# SNES-3Chip_MR_QID.net
KiCad netlist of a schematic drawn in EAGLE
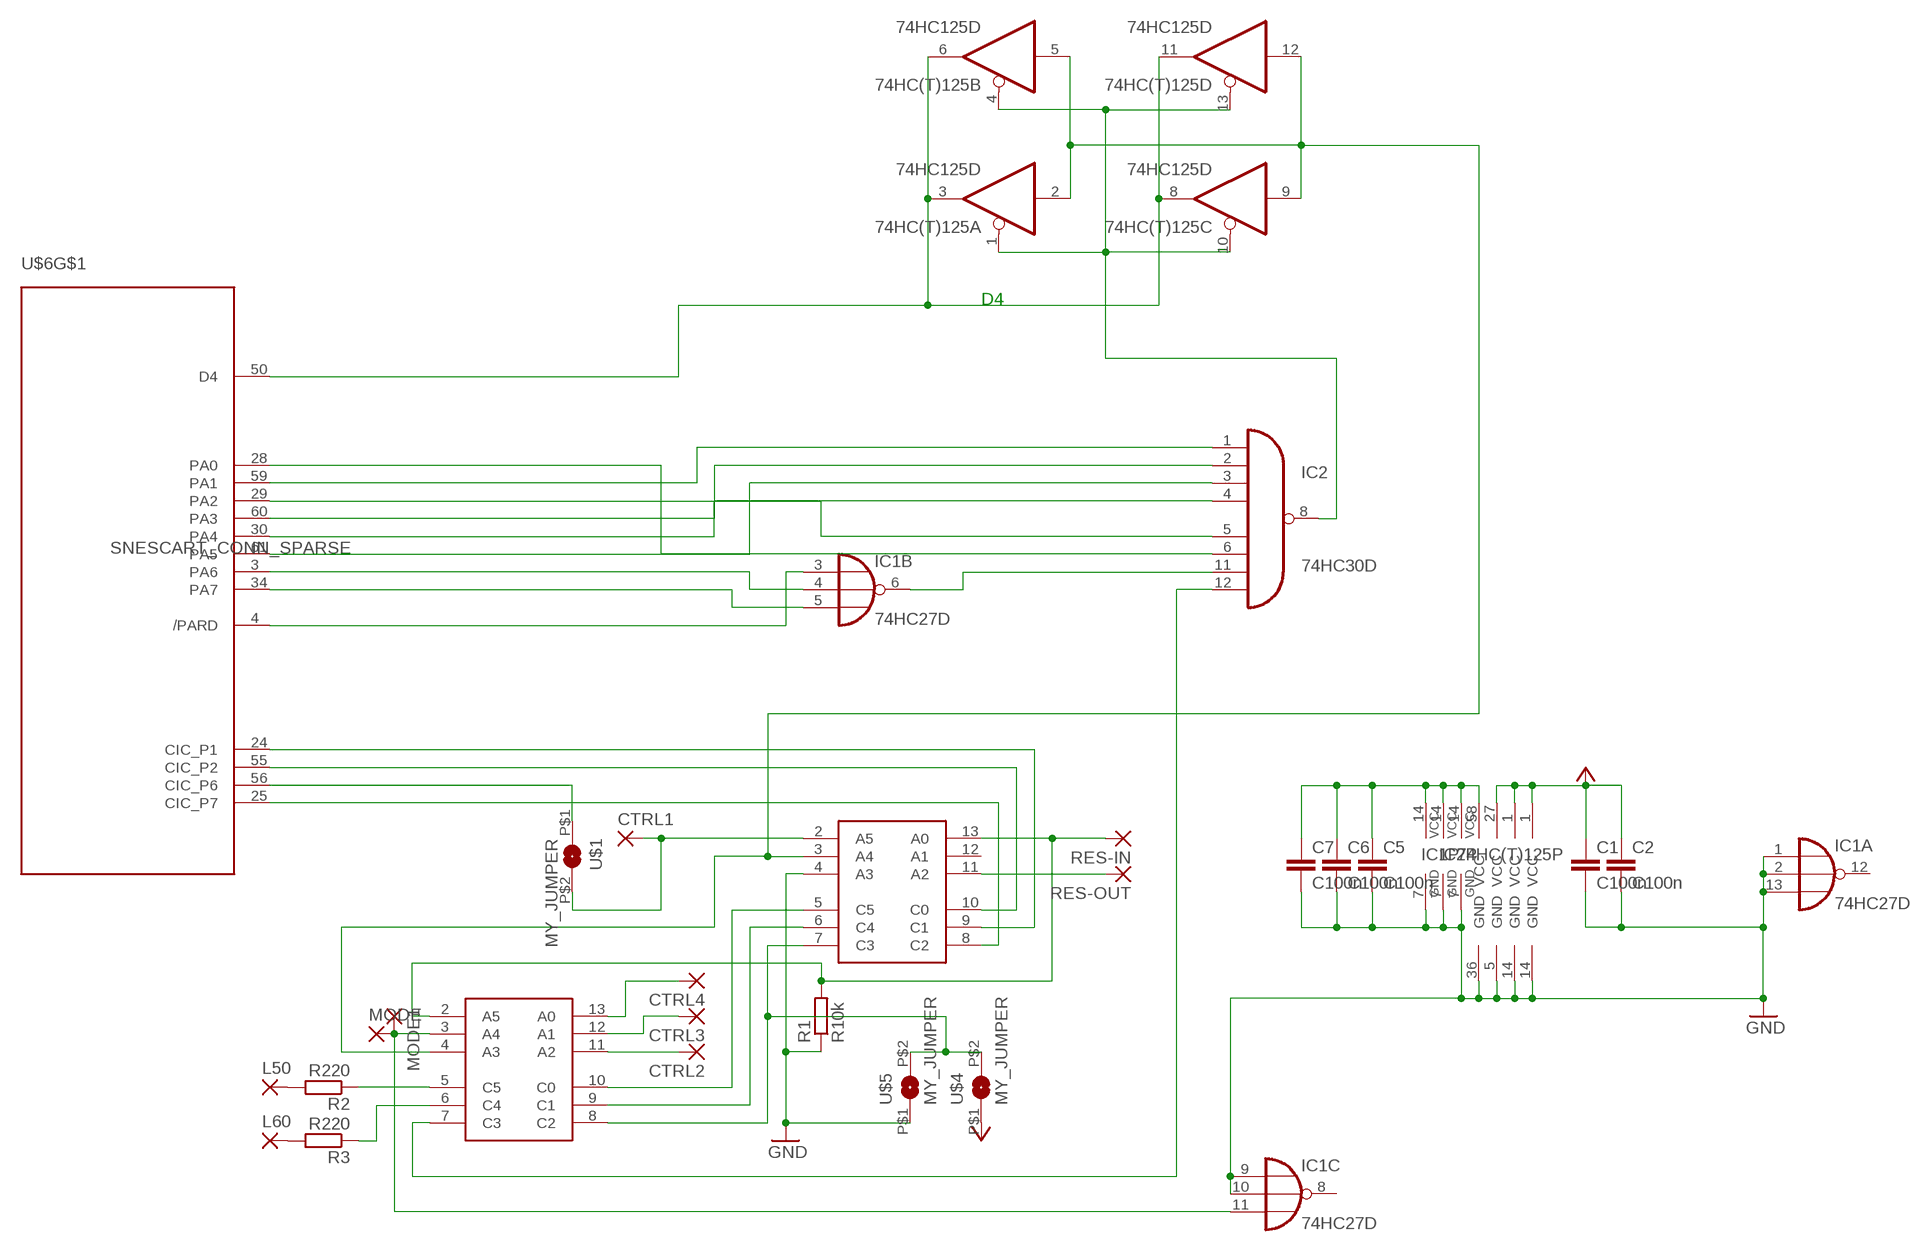
[diagram p0: schematic, sheet 1]

(export (version "E")
  (design (tool "Eeschema 10.0.6"))
  (components
    (comp (ref "74HC(T)125")
      (value "74HC125D")
      (footprint "eagle-import:SO14")
      (libsource (lib "eagle-import") (part "74125DHC"))
    )
    (comp (ref "C1")
      (value "C100n")
      (footprint "eagle-import:Z0805")
      (libsource (lib "eagle-import") (part "C0805"))
    )
    (comp (ref "C2")
      (value "C100n")
      (footprint "eagle-import:Z0805")
      (libsource (lib "eagle-import") (part "C0805"))
    )
    (comp (ref "C5")
      (value "C100n")
      (footprint "eagle-import:Z0805")
      (libsource (lib "eagle-import") (part "C0805"))
    )
    (comp (ref "C6")
      (value "C100n")
      (footprint "eagle-import:Z0805")
      (libsource (lib "eagle-import") (part "C0805"))
    )
    (comp (ref "C7")
      (value "C100n")
      (footprint "eagle-import:Z0805")
      (libsource (lib "eagle-import") (part "C0805"))
    )
    (comp (ref "CTRL1")
      (value "SMD2")
      (footprint "eagle-import:SMD1,27-2,54")
      (libsource (lib "eagle-import") (part "SMD2"))
    )
    (comp (ref "CTRL2")
      (value "SMD2")
      (footprint "eagle-import:SMD1,27-2,54")
      (libsource (lib "eagle-import") (part "SMD2"))
    )
    (comp (ref "CTRL3")
      (value "SMD2")
      (footprint "eagle-import:SMD1,27-2,54")
      (libsource (lib "eagle-import") (part "SMD2"))
    )
    (comp (ref "CTRL4")
      (value "SMD2")
      (footprint "eagle-import:SMD1,27-2,54")
      (libsource (lib "eagle-import") (part "SMD2"))
    )
    (comp (ref "IC1")
      (value "74HC27D")
      (footprint "eagle-import:SO14")
      (libsource (lib "eagle-import") (part "7427DHC"))
    )
    (comp (ref "IC2")
      (value "74HC30D")
      (footprint "eagle-import:SO14")
      (libsource (lib "eagle-import") (part "7430DHC"))
    )
    (comp (ref "L50")
      (value "SMD2")
      (footprint "eagle-import:SMD1,27-2,54")
      (libsource (lib "eagle-import") (part "SMD2"))
    )
    (comp (ref "L60")
      (value "SMD2")
      (footprint "eagle-import:SMD1,27-2,54")
      (libsource (lib "eagle-import") (part "SMD2"))
    )
    (comp (ref "MODE")
      (value "SMD2")
      (footprint "eagle-import:SMD1,27-2,54")
      (libsource (lib "eagle-import") (part "SMD2"))
    )
    (comp (ref "MODE1")
      (value "SMD2")
      (footprint "eagle-import:SMD1,27-2,54")
      (libsource (lib "eagle-import") (part "SMD2"))
    )
    (comp (ref "R1")
      (value "R10k")
      (footprint "eagle-import:Z0805")
      (libsource (lib "eagle-import") (part "R0805"))
    )
    (comp (ref "R2")
      (value "R220")
      (footprint "eagle-import:Z0805")
      (libsource (lib "eagle-import") (part "R0805"))
    )
    (comp (ref "R3")
      (value "R220")
      (footprint "eagle-import:Z0805")
      (libsource (lib "eagle-import") (part "R0805"))
    )
    (comp (ref "RES-IN")
      (value "SMD2")
      (footprint "eagle-import:SMD1,27-2,54")
      (libsource (lib "eagle-import") (part "SMD2"))
    )
    (comp (ref "RES-OUT")
      (value "SMD2")
      (footprint "eagle-import:SMD1,27-2,54")
      (libsource (lib "eagle-import") (part "SMD2"))
    )
    (comp (ref "U$1")
      (value "MY_JUMPER")
      (footprint "eagle-import:MYJUMP")
      (libsource (lib "eagle-import") (part "MY_JUMPER"))
    )
    (comp (ref "U$2")
      (value "PIC16F630_SIMPLE")
      (footprint "eagle-import:PIC16F630")
      (libsource (lib "eagle-import") (part "PIC16F630_SIMPLE"))
    )
    (comp (ref "U$3")
      (value "PIC16F630_SIMPLE")
      (footprint "eagle-import:PIC16F630")
      (libsource (lib "eagle-import") (part "PIC16F630_SIMPLE"))
    )
    (comp (ref "U$4")
      (value "MY_JUMPER")
      (footprint "eagle-import:MYJUMP")
      (libsource (lib "eagle-import") (part "MY_JUMPER"))
    )
    (comp (ref "U$5")
      (value "MY_JUMPER")
      (footprint "eagle-import:MYJUMP")
      (libsource (lib "eagle-import") (part "MY_JUMPER"))
    )
    (comp (ref "U$6")
      (value "SNESCART_CONN_SPARSE")
      (footprint "eagle-import:SNESCART_CONN_SPARSE")
      (libsource (lib "eagle-import") (part "SNESCART_CONN_SPARSE"))
    )
  )
  (nets
    (net (code "1") (name "+5V") (class "Default")
      (node (ref "C1") (pin "1") (pinfunction "1_1") (pintype "passive"))
      (node (ref "C2") (pin "1") (pinfunction "1_1") (pintype "passive"))
      (node (ref "U$2") (pin "1") (pinfunction "VCC_1") (pintype "bidirectional"))
      (node (ref "U$3") (pin "1") (pinfunction "VCC_1") (pintype "bidirectional"))
      (node (ref "U$4") (pin "P$1") (pinfunction "1_P$1") (pintype "passive"))
      (node (ref "U$6") (pin "27") (pinfunction "VCC_27") (pintype "bidirectional"))
    )
    (net (code "2") (name "GND") (class "Default")
      (node (ref "74HC(T)125") (pin "7") (pinfunction "GND_7") (pintype "power_in"))
      (node (ref "C1") (pin "2") (pinfunction "2_2") (pintype "passive"))
      (node (ref "C2") (pin "2") (pinfunction "2_2") (pintype "passive"))
      (node (ref "C5") (pin "2") (pinfunction "2_2") (pintype "passive"))
      (node (ref "C6") (pin "2") (pinfunction "2_2") (pintype "passive"))
      (node (ref "C7") (pin "2") (pinfunction "2_2") (pintype "passive"))
      (node (ref "IC1") (pin "1") (pinfunction "I0_1") (pintype "input"))
      (node (ref "IC1") (pin "10") (pinfunction "I1_10") (pintype "input"))
      (node (ref "IC1") (pin "13") (pinfunction "I2_13") (pintype "input"))
      (node (ref "IC1") (pin "2") (pinfunction "I1_2") (pintype "input"))
      (node (ref "IC1") (pin "7") (pinfunction "GND_7") (pintype "power_in"))
      (node (ref "IC1") (pin "9") (pinfunction "I0_9") (pintype "input"))
      (node (ref "IC2") (pin "7") (pinfunction "GND_7") (pintype "power_in"))
      (node (ref "R1") (pin "1") (pinfunction "1_1") (pintype "passive"))
      (node (ref "U$2") (pin "14") (pinfunction "GND_14") (pintype "bidirectional"))
      (node (ref "U$2") (pin "4") (pinfunction "A3_4") (pintype "bidirectional"))
      (node (ref "U$3") (pin "14") (pinfunction "GND_14") (pintype "bidirectional"))
      (node (ref "U$5") (pin "P$1") (pinfunction "1_P$1") (pintype "passive"))
      (node (ref "U$6") (pin "36") (pinfunction "GND_36") (pintype "bidirectional"))
      (node (ref "U$6") (pin "5") (pinfunction "GND_5") (pintype "bidirectional"))
    )
    (net (code "3") (name "Net-(74HC(T)125A-I)") (class "Default")
      (node (ref "74HC(T)125") (pin "12") (pinfunction "I_12") (pintype "input"))
      (node (ref "74HC(T)125") (pin "2") (pinfunction "I_2") (pintype "input"))
      (node (ref "74HC(T)125") (pin "5") (pinfunction "I_5") (pintype "input"))
      (node (ref "74HC(T)125") (pin "9") (pinfunction "I_9") (pintype "input"))
      (node (ref "U$2") (pin "3") (pinfunction "A4_3") (pintype "bidirectional"))
      (node (ref "U$3") (pin "4") (pinfunction "A3_4") (pintype "bidirectional"))
    )
    (net (code "4") (name "Net-(74HC(T)125A-O)") (class "Default")
      (node (ref "74HC(T)125") (pin "11") (pinfunction "O_11") (pintype "tri_state"))
      (node (ref "74HC(T)125") (pin "3") (pinfunction "O_3") (pintype "tri_state"))
      (node (ref "74HC(T)125") (pin "6") (pinfunction "O_6") (pintype "tri_state"))
      (node (ref "74HC(T)125") (pin "8") (pinfunction "O_8") (pintype "tri_state"))
      (node (ref "U$6") (pin "50") (pinfunction "D4_50") (pintype "bidirectional"))
    )
    (net (code "5") (name "Net-(74HC(T)125A-OE)") (class "Default")
      (node (ref "74HC(T)125") (pin "1") (pinfunction "OE_1") (pintype "input"))
      (node (ref "74HC(T)125") (pin "10") (pinfunction "OE_10") (pintype "input"))
      (node (ref "74HC(T)125") (pin "13") (pinfunction "OE_13") (pintype "input"))
      (node (ref "74HC(T)125") (pin "4") (pinfunction "OE_4") (pintype "input"))
      (node (ref "IC2") (pin "8") (pinfunction "O_8") (pintype "output"))
    )
    (net (code "6") (name "Net-(74HC(T)125E-VCC)") (class "Default")
      (node (ref "74HC(T)125") (pin "14") (pinfunction "VCC_14") (pintype "power_in"))
      (node (ref "C5") (pin "1") (pinfunction "1_1") (pintype "passive"))
      (node (ref "C6") (pin "1") (pinfunction "1_1") (pintype "passive"))
      (node (ref "C7") (pin "1") (pinfunction "1_1") (pintype "passive"))
      (node (ref "IC1") (pin "14") (pinfunction "VCC_14") (pintype "power_in"))
      (node (ref "IC2") (pin "14") (pinfunction "VCC_14") (pintype "power_in"))
      (node (ref "U$6") (pin "58") (pinfunction "VCC_58") (pintype "bidirectional"))
    )
    (net (code "7") (name "Net-(CTRL1-P)") (class "Default")
      (node (ref "CTRL1") (pin "1") (pinfunction "P_1") (pintype "passive"))
      (node (ref "U$1") (pin "P$2") (pinfunction "2_P$2") (pintype "passive"))
      (node (ref "U$2") (pin "2") (pinfunction "A5_2") (pintype "bidirectional"))
    )
    (net (code "8") (name "Net-(CTRL2-P)") (class "Default")
      (node (ref "CTRL2") (pin "1") (pinfunction "P_1") (pintype "passive"))
      (node (ref "U$3") (pin "11") (pinfunction "A2_11") (pintype "bidirectional"))
    )
    (net (code "9") (name "Net-(CTRL3-P)") (class "Default")
      (node (ref "CTRL3") (pin "1") (pinfunction "P_1") (pintype "passive"))
      (node (ref "U$3") (pin "12") (pinfunction "A1_12") (pintype "bidirectional"))
    )
    (net (code "10") (name "Net-(CTRL4-P)") (class "Default")
      (node (ref "CTRL4") (pin "1") (pinfunction "P_1") (pintype "passive"))
      (node (ref "U$3") (pin "13") (pinfunction "A0_13") (pintype "bidirectional"))
    )
    (net (code "11") (name "Net-(IC1B-I0)") (class "Default")
      (node (ref "IC1") (pin "3") (pinfunction "I0_3") (pintype "input"))
      (node (ref "U$6") (pin "4") (pinfunction "/PARD_4") (pintype "bidirectional"))
    )
    (net (code "12") (name "Net-(IC1B-I1)") (class "Default")
      (node (ref "IC1") (pin "4") (pinfunction "I1_4") (pintype "input"))
      (node (ref "U$6") (pin "3") (pinfunction "PA6_3") (pintype "bidirectional"))
    )
    (net (code "13") (name "Net-(IC1B-I2)") (class "Default")
      (node (ref "IC1") (pin "5") (pinfunction "I2_5") (pintype "input"))
      (node (ref "U$6") (pin "34") (pinfunction "PA7_34") (pintype "bidirectional"))
    )
    (net (code "14") (name "Net-(IC1B-O)") (class "Default")
      (node (ref "IC1") (pin "6") (pinfunction "O_6") (pintype "output"))
      (node (ref "IC2") (pin "11") (pinfunction "I6_11") (pintype "input"))
    )
    (net (code "15") (name "Net-(IC1C-I2)") (class "Default")
      (node (ref "IC1") (pin "11") (pinfunction "I2_11") (pintype "input"))
      (node (ref "MODE") (pin "1") (pinfunction "P_1") (pintype "passive"))
      (node (ref "MODE1") (pin "1") (pinfunction "P_1") (pintype "passive"))
      (node (ref "U$3") (pin "3") (pinfunction "A4_3") (pintype "bidirectional"))
    )
    (net (code "16") (name "Net-(IC2A-I0)") (class "Default")
      (node (ref "IC2") (pin "1") (pinfunction "I0_1") (pintype "input"))
      (node (ref "U$6") (pin "59") (pinfunction "PA1_59") (pintype "bidirectional"))
    )
    (net (code "17") (name "Net-(IC2A-I1)") (class "Default")
      (node (ref "IC2") (pin "2") (pinfunction "I1_2") (pintype "input"))
      (node (ref "U$6") (pin "60") (pinfunction "PA3_60") (pintype "bidirectional"))
    )
    (net (code "18") (name "Net-(IC2A-I2)") (class "Default")
      (node (ref "IC2") (pin "3") (pinfunction "I2_3") (pintype "input"))
      (node (ref "U$6") (pin "61") (pinfunction "PA5_61") (pintype "bidirectional"))
    )
    (net (code "19") (name "Net-(IC2A-I3)") (class "Default")
      (node (ref "IC2") (pin "4") (pinfunction "I3_4") (pintype "input"))
      (node (ref "U$6") (pin "30") (pinfunction "PA4_30") (pintype "bidirectional"))
    )
    (net (code "20") (name "Net-(IC2A-I4)") (class "Default")
      (node (ref "IC2") (pin "5") (pinfunction "I4_5") (pintype "input"))
      (node (ref "U$6") (pin "29") (pinfunction "PA2_29") (pintype "bidirectional"))
    )
    (net (code "21") (name "Net-(IC2A-I5)") (class "Default")
      (node (ref "IC2") (pin "6") (pinfunction "I5_6") (pintype "input"))
      (node (ref "U$6") (pin "28") (pinfunction "PA0_28") (pintype "bidirectional"))
    )
    (net (code "22") (name "Net-(IC2A-I7)") (class "Default")
      (node (ref "IC2") (pin "12") (pinfunction "I7_12") (pintype "input"))
      (node (ref "U$3") (pin "7") (pinfunction "C3_7") (pintype "bidirectional"))
    )
    (net (code "23") (name "Net-(L50-P)") (class "Default")
      (node (ref "L50") (pin "1") (pinfunction "P_1") (pintype "passive"))
      (node (ref "R2") (pin "2") (pinfunction "2_2") (pintype "passive"))
    )
    (net (code "24") (name "Net-(L60-P)") (class "Default")
      (node (ref "L60") (pin "1") (pinfunction "P_1") (pintype "passive"))
      (node (ref "R3") (pin "2") (pinfunction "2_2") (pintype "passive"))
    )
    (net (code "25") (name "Net-(RES-IN-P)") (class "Default")
      (node (ref "R1") (pin "2") (pinfunction "2_2") (pintype "passive"))
      (node (ref "RES-IN") (pin "1") (pinfunction "P_1") (pintype "passive"))
      (node (ref "U$2") (pin "13") (pinfunction "A0_13") (pintype "bidirectional"))
      (node (ref "U$3") (pin "2") (pinfunction "A5_2") (pintype "bidirectional"))
    )
    (net (code "26") (name "Net-(RES-OUT-P)") (class "Default")
      (node (ref "RES-OUT") (pin "1") (pinfunction "P_1") (pintype "passive"))
      (node (ref "U$2") (pin "11") (pinfunction "A2_11") (pintype "bidirectional"))
    )
    (net (code "27") (name "Net-(U$1-1)") (class "Default")
      (node (ref "U$1") (pin "P$1") (pinfunction "1_P$1") (pintype "passive"))
      (node (ref "U$6") (pin "56") (pinfunction "CIC_P6_56") (pintype "bidirectional"))
    )
    (net (code "28") (name "Net-(U$2A-C0)") (class "Default")
      (node (ref "U$2") (pin "10") (pinfunction "C0_10") (pintype "bidirectional"))
      (node (ref "U$6") (pin "55") (pinfunction "CIC_P2_55") (pintype "bidirectional"))
    )
    (net (code "29") (name "Net-(U$2A-C1)") (class "Default")
      (node (ref "U$2") (pin "9") (pinfunction "C1_9") (pintype "bidirectional"))
      (node (ref "U$6") (pin "24") (pinfunction "CIC_P1_24") (pintype "bidirectional"))
    )
    (net (code "30") (name "Net-(U$2A-C2)") (class "Default")
      (node (ref "U$2") (pin "8") (pinfunction "C2_8") (pintype "bidirectional"))
      (node (ref "U$6") (pin "25") (pinfunction "CIC_P7_25") (pintype "bidirectional"))
    )
    (net (code "31") (name "Net-(U$2A-C3)") (class "Default")
      (node (ref "U$2") (pin "7") (pinfunction "C3_7") (pintype "bidirectional"))
      (node (ref "U$3") (pin "8") (pinfunction "C2_8") (pintype "bidirectional"))
      (node (ref "U$4") (pin "P$2") (pinfunction "2_P$2") (pintype "passive"))
      (node (ref "U$5") (pin "P$2") (pinfunction "2_P$2") (pintype "passive"))
    )
    (net (code "32") (name "Net-(U$2A-C4)") (class "Default")
      (node (ref "U$2") (pin "6") (pinfunction "C4_6") (pintype "bidirectional"))
      (node (ref "U$3") (pin "9") (pinfunction "C1_9") (pintype "bidirectional"))
    )
    (net (code "33") (name "Net-(U$2A-C5)") (class "Default")
      (node (ref "U$2") (pin "5") (pinfunction "C5_5") (pintype "bidirectional"))
      (node (ref "U$3") (pin "10") (pinfunction "C0_10") (pintype "bidirectional"))
    )
    (net (code "34") (name "Net-(U$3A-C4)") (class "Default")
      (node (ref "R3") (pin "1") (pinfunction "1_1") (pintype "passive"))
      (node (ref "U$3") (pin "6") (pinfunction "C4_6") (pintype "bidirectional"))
    )
    (net (code "35") (name "Net-(U$3A-C5)") (class "Default")
      (node (ref "R2") (pin "1") (pinfunction "1_1") (pintype "passive"))
      (node (ref "U$3") (pin "5") (pinfunction "C5_5") (pintype "bidirectional"))
    )
    (net (code "36") (name "unconnected-(IC1A-O-Pad12)") (class "Default")
      (node (ref "IC1") (pin "12") (pinfunction "O_12") (pintype "output"))
    )
    (net (code "37") (name "unconnected-(IC1C-O-Pad8)") (class "Default")
      (node (ref "IC1") (pin "8") (pinfunction "O_8") (pintype "output"))
    )
    (net (code "38") (name "unconnected-(U$2A-A1-Pad12)") (class "Default")
      (node (ref "U$2") (pin "12") (pinfunction "A1_12") (pintype "bidirectional"))
    )
  )
)
